# 1-Schematic.net
KiCad netlist of a schematic drawn in EasyEDA
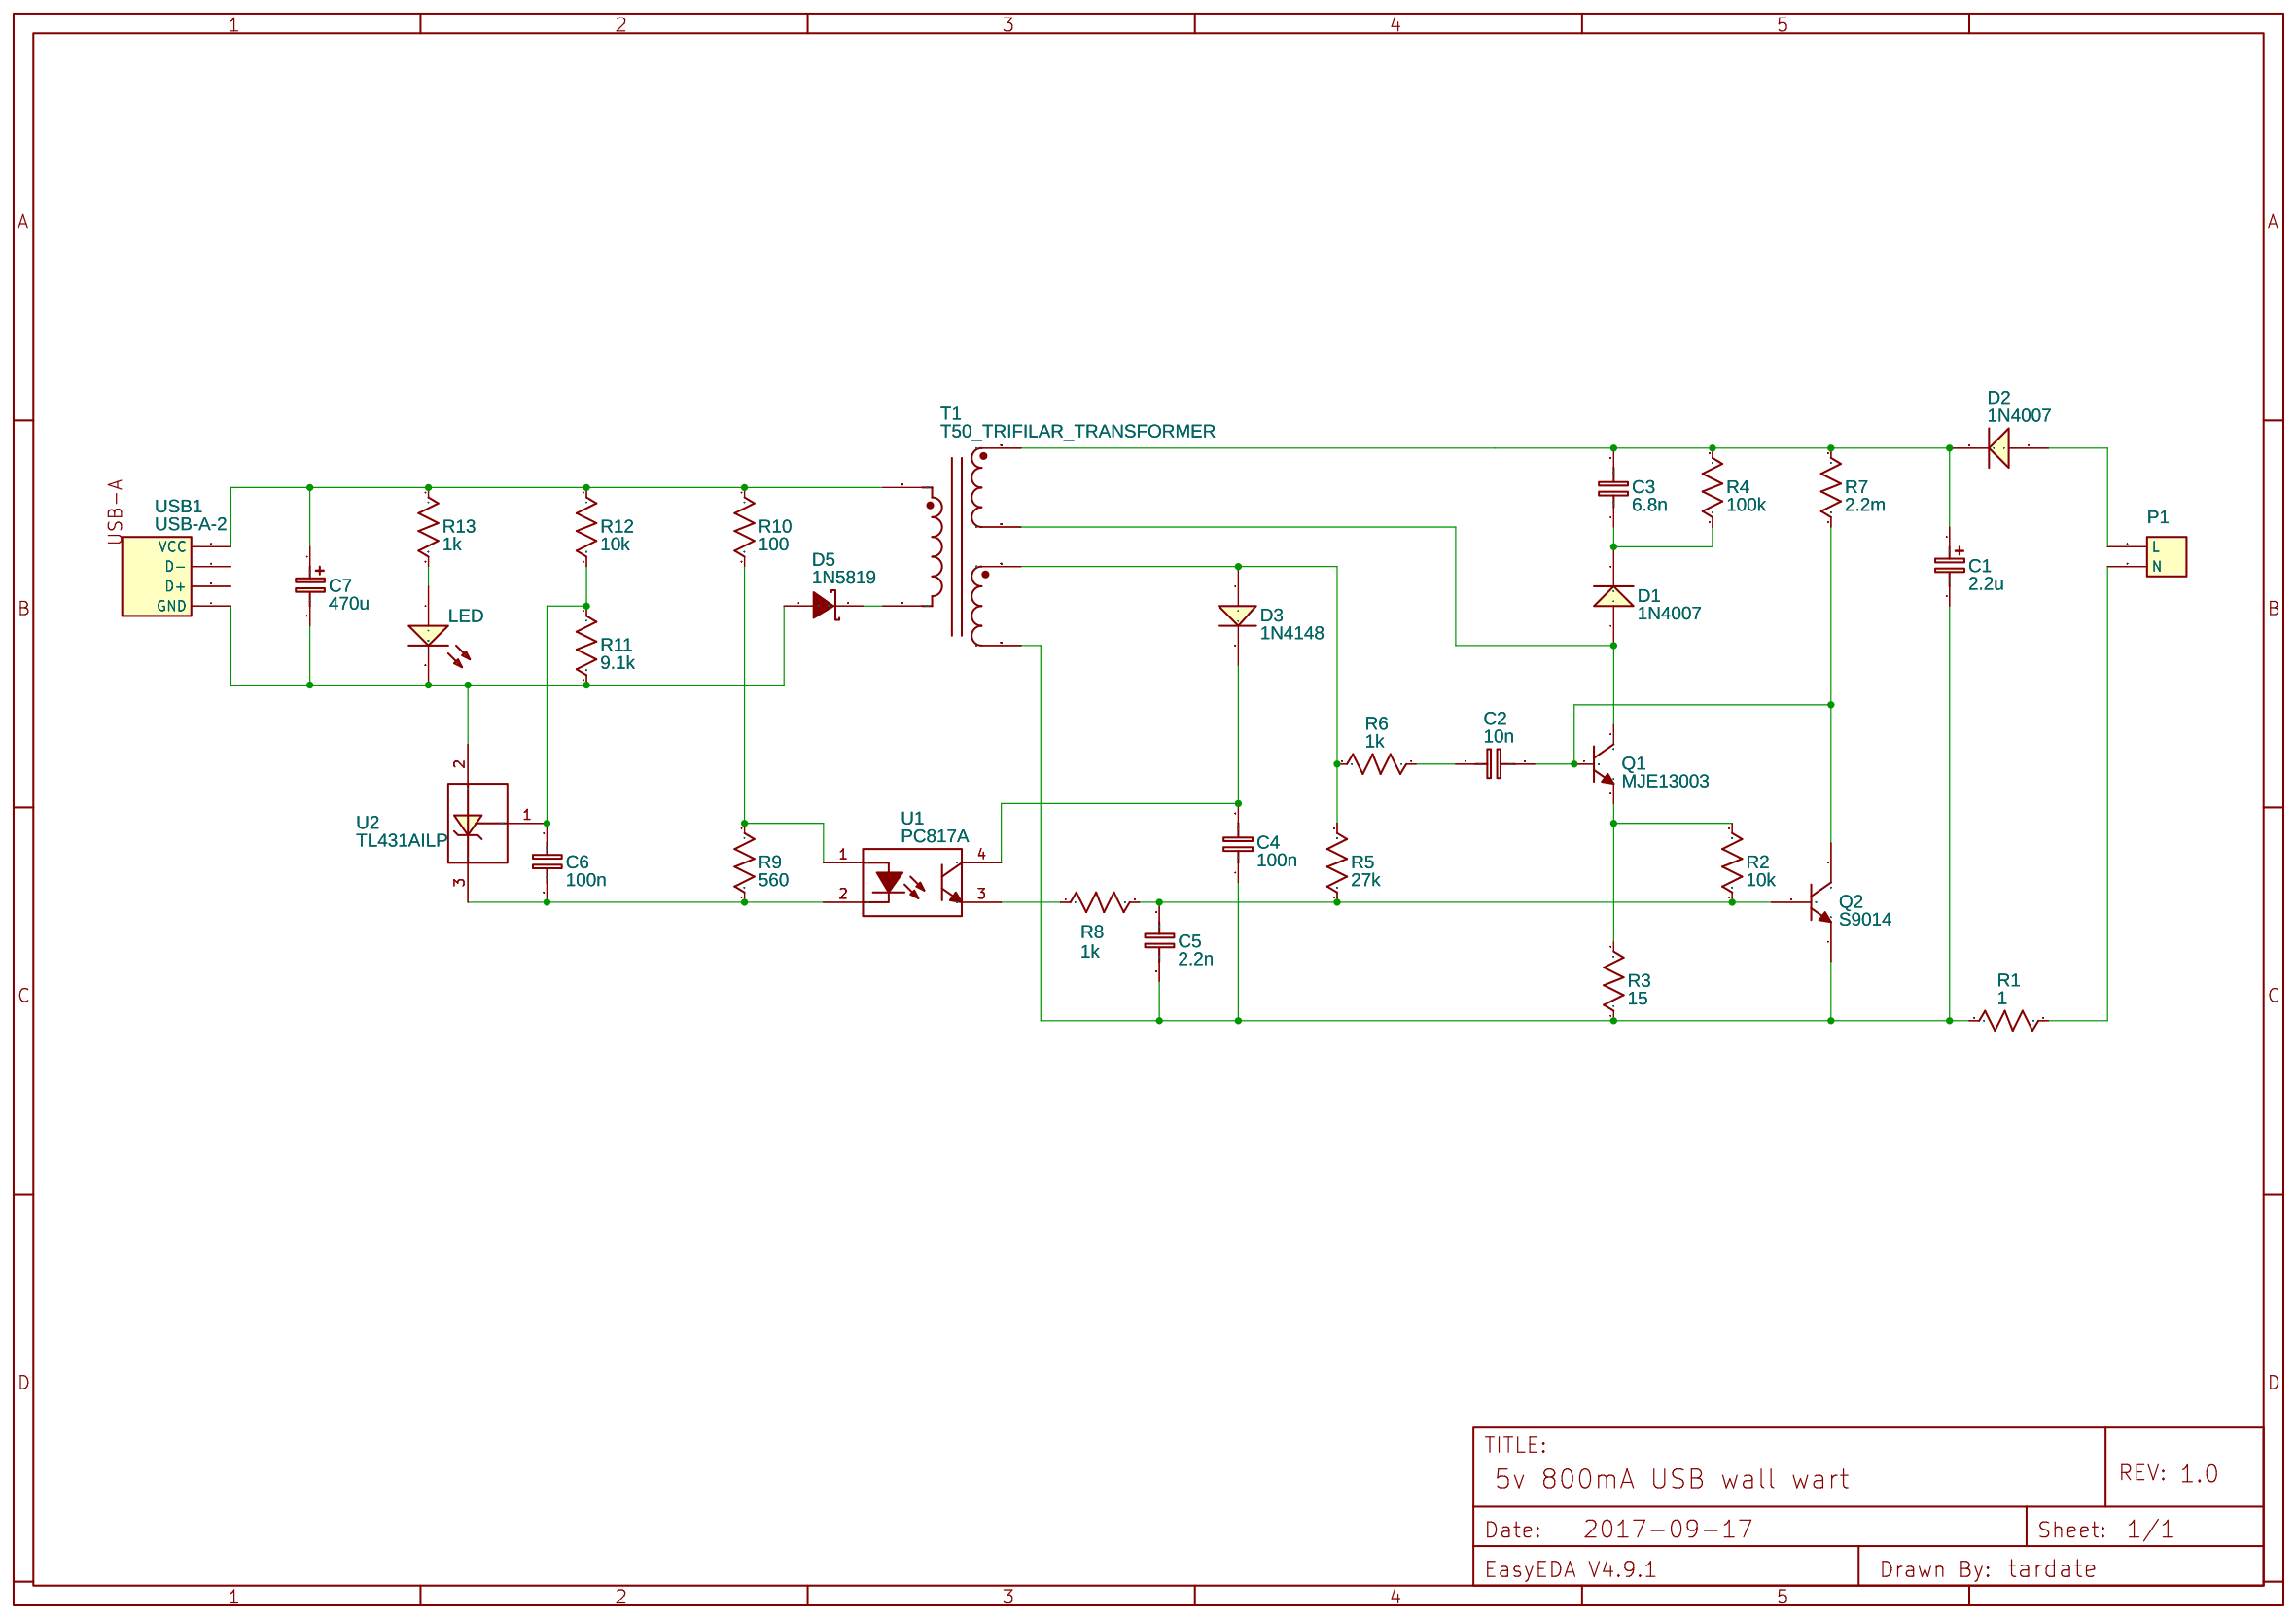
[diagram p0: schematic sheet]

(export (version "E")
  (design (tool "Eeschema 10.0.6"))
  (components
    (comp (ref "C1")
      (value "2.2u")
      (fields (field (name "BOM_Manufacturer Part") "?"))
      (libsource (lib "") (part "Capacitor"))
    )
    (comp (ref "C2")
      (value "10n")
      (fields (field (name "BOM_Manufacturer Part") "?"))
      (libsource (lib "") (part "Capacitor_3"))
    )
    (comp (ref "C3")
      (value "6.8n")
      (fields (field (name "BOM_Manufacturer Part") "?"))
      (libsource (lib "") (part "Capacitor_2"))
    )
    (comp (ref "C4")
      (value "100n")
      (fields (field (name "BOM_Manufacturer Part") "?"))
      (libsource (lib "") (part "Capacitor_2"))
    )
    (comp (ref "C5")
      (value "2.2n")
      (fields (field (name "BOM_Manufacturer Part") "?"))
      (libsource (lib "") (part "Capacitor_5"))
    )
    (comp (ref "C6")
      (value "100n")
      (fields (field (name "BOM_Manufacturer Part") "?"))
      (libsource (lib "") (part "Capacitor_4"))
    )
    (comp (ref "C7")
      (value "470u")
      (fields (field (name "BOM_Manufacturer Part") "?"))
      (libsource (lib "") (part "Capacitor_1"))
    )
    (comp (ref "D1")
      (value "1N4007")
      (fields (field (name "BOM_Manufacturer Part") "?"))
      (libsource (lib "") (part "Unknown_810_300"))
    )
    (comp (ref "D2")
      (value "1N4007")
      (fields (field (name "BOM_Manufacturer Part") "?"))
      (libsource (lib "") (part "Unknown_1010_220"))
    )
    (comp (ref "D3")
      (value "1N4148")
      (fields (field (name "BOM_Manufacturer Part") "?"))
      (libsource (lib "") (part "Unknown_620_300"))
    )
    (comp (ref "D5") (value "1N5819") (libsource (lib "") (part "Unknown_410_300")))
    (comp (ref "LED") (value "204-10UYC/S530-A3") (libsource (lib "") (part "Unknown_210_320")))
    (comp (ref "P1") (value "Header-Female-2.54_1x2") (libsource (lib "") (part "Unknown_1070_280")))
    (comp (ref "Q1") (value "MJE13003") (libsource (lib "") (part "Unknown_800_380")))
    (comp (ref "Q2")
      (value "S9014")
      (fields (field (name "BOM_Manufacturer Part") "S9014 Tube"))
      (libsource (lib "") (part "Unknown_910_450"))
    )
    (comp (ref "R1")
      (value "1")
      (fields (field (name "BOM_Manufacturer Part") "?"))
      (libsource (lib "") (part "Resistor"))
    )
    (comp (ref "R2")
      (value "10k")
      (fields (field (name "BOM_Manufacturer Part") "?"))
      (libsource (lib "") (part "Resistor_1"))
    )
    (comp (ref "R3")
      (value "15")
      (fields (field (name "BOM_Manufacturer Part") "?"))
      (libsource (lib "") (part "Resistor_1"))
    )
    (comp (ref "R4")
      (value "100k")
      (fields (field (name "BOM_Manufacturer Part") "?"))
      (libsource (lib "") (part "Resistor_1"))
    )
    (comp (ref "R5")
      (value "27k")
      (fields (field (name "BOM_Manufacturer Part") "?"))
      (libsource (lib "") (part "Resistor_1"))
    )
    (comp (ref "R6")
      (value "1k")
      (fields (field (name "BOM_Manufacturer Part") "?"))
      (libsource (lib "") (part "Resistor_3"))
    )
    (comp (ref "R7")
      (value "2.2m")
      (fields (field (name "BOM_Manufacturer Part") "?"))
      (libsource (lib "") (part "Resistor_2"))
    )
    (comp (ref "R8")
      (value "1k")
      (fields (field (name "BOM_Manufacturer Part") "?"))
      (libsource (lib "") (part "Resistor"))
    )
    (comp (ref "R9")
      (value "560")
      (fields (field (name "BOM_Manufacturer Part") "?"))
      (libsource (lib "") (part "Resistor_2"))
    )
    (comp (ref "R10")
      (value "100")
      (fields (field (name "BOM_Manufacturer Part") "?"))
      (libsource (lib "") (part "Resistor_2"))
    )
    (comp (ref "R11")
      (value "9.1k")
      (fields (field (name "BOM_Manufacturer Part") "?"))
      (libsource (lib "") (part "Resistor_2"))
    )
    (comp (ref "R12")
      (value "10k")
      (fields (field (name "BOM_Manufacturer Part") "?"))
      (libsource (lib "") (part "Resistor_2"))
    )
    (comp (ref "R13")
      (value "1k")
      (fields (field (name "BOM_Manufacturer Part") "?"))
      (libsource (lib "") (part "Resistor_2"))
    )
    (comp (ref "T1")
      (value "T50_TRIFILAR_TRANSFORMER")
      (fields (field (name "BOM_Manufacturer Part") "?"))
      (libsource (lib "") (part "Unknown_480_270"))
    )
    (comp (ref "U1")
      (value "PC817A")
      (fields (field (name "BOM_Manufacturer Part") "PC817X1NSZW"))
      (libsource (lib "") (part "Unknown_460_440"))
    )
    (comp (ref "U2")
      (value "TL431AILP")
      (fields (field (name "BOM_Manufacturer Part") "?"))
      (libsource (lib "") (part "Unknown_240_410"))
    )
    (comp (ref "USB1") (value "USB-A-2") (libsource (lib "") (part "Unknown_100_290")))
  )
  (nets
    (net (code "1") (name "Net-(C2-Pad1)") (class "Default")
      (node (ref "C2") (pin "1") (pinfunction "1_1") (pintype "unspecified"))
      (node (ref "R6") (pin "1") (pinfunction "1_1") (pintype "unspecified"))
    )
    (net (code "2") (name "Net-(D1-A)") (class "Default")
      (node (ref "D1") (pin "1") (pinfunction "A_1") (pintype "unspecified"))
      (node (ref "Q1") (pin "2") (pinfunction "C_2") (pintype "unspecified"))
      (node (ref "T1") (pin "C2A") (pinfunction "C2A_C2A") (pintype "unspecified"))
    )
    (net (code "3") (name "Net-(D1-K)") (class "Default")
      (node (ref "C3") (pin "1") (pinfunction "1_1") (pintype "unspecified"))
      (node (ref "D1") (pin "2") (pinfunction "K_2") (pintype "unspecified"))
      (node (ref "R4") (pin "1") (pinfunction "1_1") (pintype "unspecified"))
    )
    (net (code "4") (name "Net-(D2-A)") (class "Default")
      (node (ref "D2") (pin "1") (pinfunction "A_1") (pintype "unspecified"))
      (node (ref "P1") (pin "1") (pinfunction "L_1") (pintype "input"))
    )
    (net (code "5") (name "Net-(D2-K)") (class "Default")
      (node (ref "C1") (pin "1") (pinfunction "1_1") (pintype "unspecified"))
      (node (ref "C3") (pin "2") (pinfunction "2_2") (pintype "unspecified"))
      (node (ref "D2") (pin "2") (pinfunction "K_2") (pintype "unspecified"))
      (node (ref "R4") (pin "2") (pinfunction "2_2") (pintype "unspecified"))
      (node (ref "R7") (pin "1") (pinfunction "1_1") (pintype "unspecified"))
      (node (ref "T1") (pin "C2B") (pinfunction "C2B_C2B") (pintype "unspecified"))
    )
    (net (code "6") (name "Net-(D3-A)") (class "Default")
      (node (ref "D3") (pin "1") (pinfunction "A_1") (pintype "unspecified"))
      (node (ref "R5") (pin "2") (pinfunction "2_2") (pintype "unspecified"))
      (node (ref "R6") (pin "2") (pinfunction "2_2") (pintype "unspecified"))
      (node (ref "T1") (pin "C3B") (pinfunction "C3B_C3B") (pintype "unspecified"))
    )
    (net (code "7") (name "Net-(D3-K)") (class "Default")
      (node (ref "C4") (pin "2") (pinfunction "2_2") (pintype "unspecified"))
      (node (ref "D3") (pin "2") (pinfunction "K_2") (pintype "unspecified"))
      (node (ref "U1") (pin "4") (pinfunction "4_4") (pintype "unspecified"))
    )
    (net (code "8") (name "Net-(D5-A)") (class "Default")
      (node (ref "C7") (pin "2") (pinfunction "2_2") (pintype "unspecified"))
      (node (ref "D5") (pin "1") (pinfunction "A_1") (pintype "unspecified"))
      (node (ref "LED") (pin "2") (pinfunction "C_2") (pintype "input"))
      (node (ref "R11") (pin "2") (pinfunction "2_2") (pintype "unspecified"))
      (node (ref "U2") (pin "2") (pinfunction "A_2") (pintype "unspecified"))
      (node (ref "USB1") (pin "4") (pinfunction "GND_4") (pintype "input"))
    )
    (net (code "9") (name "Net-(D5-K)") (class "Default")
      (node (ref "D5") (pin "2") (pinfunction "K_2") (pintype "unspecified"))
      (node (ref "T1") (pin "C1A") (pinfunction "C1A_C1A") (pintype "unspecified"))
    )
    (net (code "10") (name "Net-(LED-A)") (class "Default")
      (node (ref "LED") (pin "1") (pinfunction "A_1") (pintype "input"))
      (node (ref "R13") (pin "2") (pinfunction "2_2") (pintype "unspecified"))
    )
    (net (code "11") (name "Net-(P1-N)") (class "Default")
      (node (ref "P1") (pin "2") (pinfunction "N_2") (pintype "input"))
      (node (ref "R1") (pin "2") (pinfunction "2_2") (pintype "unspecified"))
    )
    (net (code "12") (name "Net-(Q1-B)") (class "Default")
      (node (ref "C2") (pin "2") (pinfunction "2_2") (pintype "unspecified"))
      (node (ref "Q1") (pin "1") (pinfunction "B_1") (pintype "unspecified"))
      (node (ref "Q2") (pin "3") (pinfunction "C_3") (pintype "unspecified"))
      (node (ref "R7") (pin "2") (pinfunction "2_2") (pintype "unspecified"))
    )
    (net (code "13") (name "Net-(Q1-E)") (class "Default")
      (node (ref "Q1") (pin "3") (pinfunction "E_3") (pintype "unspecified"))
      (node (ref "R2") (pin "2") (pinfunction "2_2") (pintype "unspecified"))
      (node (ref "R3") (pin "2") (pinfunction "2_2") (pintype "unspecified"))
    )
    (net (code "14") (name "Net-(Q2-B)") (class "Default")
      (node (ref "C5") (pin "1") (pinfunction "1_1") (pintype "unspecified"))
      (node (ref "Q2") (pin "2") (pinfunction "B_2") (pintype "unspecified"))
      (node (ref "R2") (pin "1") (pinfunction "1_1") (pintype "unspecified"))
      (node (ref "R5") (pin "1") (pinfunction "1_1") (pintype "unspecified"))
      (node (ref "R8") (pin "2") (pinfunction "2_2") (pintype "unspecified"))
    )
    (net (code "15") (name "Net-(Q2-E)") (class "Default")
      (node (ref "C1") (pin "2") (pinfunction "2_2") (pintype "unspecified"))
      (node (ref "C4") (pin "1") (pinfunction "1_1") (pintype "unspecified"))
      (node (ref "C5") (pin "2") (pinfunction "2_2") (pintype "unspecified"))
      (node (ref "Q2") (pin "1") (pinfunction "E_1") (pintype "unspecified"))
      (node (ref "R1") (pin "1") (pinfunction "1_1") (pintype "unspecified"))
      (node (ref "R3") (pin "1") (pinfunction "1_1") (pintype "unspecified"))
      (node (ref "T1") (pin "C3A") (pinfunction "C3A_C3A") (pintype "unspecified"))
    )
    (net (code "16") (name "Net-(R8-Pad1)") (class "Default")
      (node (ref "R8") (pin "1") (pinfunction "1_1") (pintype "unspecified"))
      (node (ref "U1") (pin "3") (pinfunction "3_3") (pintype "unspecified"))
    )
    (net (code "17") (name "Net-(R10-Pad2)") (class "Default")
      (node (ref "R10") (pin "2") (pinfunction "2_2") (pintype "unspecified"))
      (node (ref "R9") (pin "1") (pinfunction "1_1") (pintype "unspecified"))
      (node (ref "U1") (pin "1") (pinfunction "1_1") (pintype "unspecified"))
    )
    (net (code "18") (name "Net-(U2-K)") (class "Default")
      (node (ref "C6") (pin "2") (pinfunction "2_2") (pintype "unspecified"))
      (node (ref "R9") (pin "2") (pinfunction "2_2") (pintype "unspecified"))
      (node (ref "U1") (pin "2") (pinfunction "2_2") (pintype "unspecified"))
      (node (ref "U2") (pin "3") (pinfunction "K_3") (pintype "unspecified"))
    )
    (net (code "19") (name "Net-(U2-REF)") (class "Default")
      (node (ref "C6") (pin "1") (pinfunction "1_1") (pintype "unspecified"))
      (node (ref "R11") (pin "1") (pinfunction "1_1") (pintype "unspecified"))
      (node (ref "R12") (pin "2") (pinfunction "2_2") (pintype "unspecified"))
      (node (ref "U2") (pin "1") (pinfunction "REF_1") (pintype "unspecified"))
    )
    (net (code "20") (name "Net-(USB1-VCC)") (class "Default")
      (node (ref "C7") (pin "1") (pinfunction "1_1") (pintype "unspecified"))
      (node (ref "R10") (pin "1") (pinfunction "1_1") (pintype "unspecified"))
      (node (ref "R12") (pin "1") (pinfunction "1_1") (pintype "unspecified"))
      (node (ref "R13") (pin "1") (pinfunction "1_1") (pintype "unspecified"))
      (node (ref "T1") (pin "C1B") (pinfunction "C1B_C1B") (pintype "unspecified"))
      (node (ref "USB1") (pin "1") (pinfunction "VCC_1") (pintype "input"))
    )
    (net (code "21") (name "unconnected-(USB1-D+-Pad3)") (class "Default")
      (node (ref "USB1") (pin "3") (pinfunction "D+_3") (pintype "input"))
    )
    (net (code "22") (name "unconnected-(USB1-D--Pad2)") (class "Default")
      (node (ref "USB1") (pin "2") (pinfunction "D-_2") (pintype "input"))
    )
  )
)
